# usbToTTLByPL2303_6.net
KiCad netlist of a schematic drawn in Altium Designer
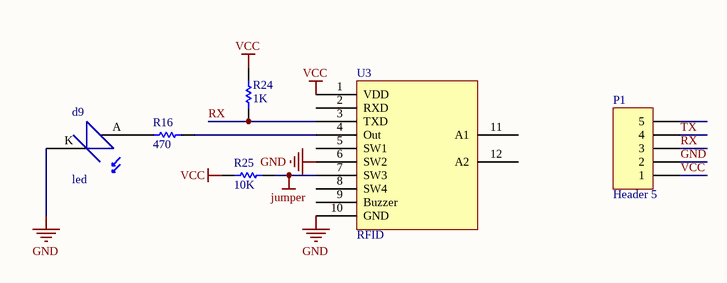
[diagram p0: usbToTTLByPL2303_6.SchDoc]

(export (version "E")
  (design (tool "Eeschema 10.0.6"))
  (components
    (comp (ref "d9") (value "led") (footprint "LED5") (libsource (lib "SchLib306") (part "led")))
    (comp (ref "P1")
      (value "Header 5")
      (footprint "HDR1X5")
      (description "Header, 5-Pin")
      (fields (field (name "PUBLISHER") "Altium Limited"))
      (libsource (lib "Miscellaneous Connectors") (part "Header 5"))
    )
    (comp (ref "R16")
      (value "470")
      (footprint "1206_smd")
      (description "Resistor")
      (fields (field (name "PUBLISHER") "Altium Limited"))
      (libsource (lib "Miscellaneous Devices") (part "Res1"))
    )
    (comp (ref "R24")
      (value "1K")
      (footprint "1206_smd")
      (description "Resistor")
      (fields (field (name "PUBLISHER") "Altium Limited"))
      (libsource (lib "Miscellaneous Devices") (part "Res1"))
    )
    (comp (ref "R25")
      (value "10K")
      (footprint "1206_smd")
      (description "Resistor")
      (fields (field (name "PUBLISHER") "Altium Limited"))
      (libsource (lib "Miscellaneous Devices") (part "Res1"))
    )
    (comp (ref "U3") (value "RFID") (footprint "rf") (libsource (lib "SchLib306") (part "RFID module")))
  )
  (nets
    (net (code "1") (name "/RX") (class "Default")
      (node (ref "P1") (pin "3") (pinfunction "3_3") (pintype "passive"))
      (node (ref "R24") (pin "1") (pinfunction "1_1") (pintype "passive"))
      (node (ref "U3") (pin "3") (pinfunction "TXD_3") (pintype "passive"))
    )
    (net (code "2") (name "/TX") (class "Default")
      (node (ref "P1") (pin "4") (pinfunction "4_4") (pintype "passive"))
    )
    (net (code "3") (name "GND") (class "Default")
      (node (ref "P1") (pin "2") (pinfunction "2_2") (pintype "passive"))
      (node (ref "U3") (pin "10") (pinfunction "GND_10") (pintype "passive"))
      (node (ref "U3") (pin "6") (pinfunction "SW2_6") (pintype "passive"))
      (node (ref "d9") (pin "K") (pintype "passive"))
    )
    (net (code "4") (name "Net-(R16-Pad1)") (class "Default")
      (node (ref "R16") (pin "1") (pinfunction "1_1") (pintype "passive"))
      (node (ref "d9") (pin "A") (pintype "passive"))
    )
    (net (code "5") (name "Net-(U3-Out)") (class "Default")
      (node (ref "R16") (pin "2") (pinfunction "2_2") (pintype "passive"))
      (node (ref "U3") (pin "4") (pinfunction "Out_4") (pintype "passive"))
    )
    (net (code "6") (name "VCC") (class "Default")
      (node (ref "P1") (pin "1") (pinfunction "1_1") (pintype "passive"))
      (node (ref "R24") (pin "2") (pinfunction "2_2") (pintype "passive"))
      (node (ref "R25") (pin "2") (pinfunction "2_2") (pintype "passive"))
      (node (ref "U3") (pin "1") (pinfunction "VDD_1") (pintype "passive"))
    )
    (net (code "7") (name "jumper") (class "Default")
      (node (ref "R25") (pin "1") (pinfunction "1_1") (pintype "passive"))
      (node (ref "U3") (pin "7") (pinfunction "SW3_7") (pintype "passive"))
    )
    (net (code "8") (name "unconnected-(P1-Pad5)") (class "Default")
      (node (ref "P1") (pin "5") (pinfunction "5_5") (pintype "passive"))
    )
    (net (code "9") (name "unconnected-(U3-A1-Pad11)") (class "Default")
      (node (ref "U3") (pin "11") (pinfunction "A1_11") (pintype "passive"))
    )
    (net (code "10") (name "unconnected-(U3-A2-Pad12)") (class "Default")
      (node (ref "U3") (pin "12") (pinfunction "A2_12") (pintype "passive"))
    )
    (net (code "11") (name "unconnected-(U3-Buzzer-Pad9)") (class "Default")
      (node (ref "U3") (pin "9") (pinfunction "Buzzer_9") (pintype "passive"))
    )
    (net (code "12") (name "unconnected-(U3-RXD-Pad2)") (class "Default")
      (node (ref "U3") (pin "2") (pinfunction "RXD_2") (pintype "passive"))
    )
    (net (code "13") (name "unconnected-(U3-SW1-Pad5)") (class "Default")
      (node (ref "U3") (pin "5") (pinfunction "SW1_5") (pintype "passive"))
    )
    (net (code "14") (name "unconnected-(U3-SW4-Pad8)") (class "Default")
      (node (ref "U3") (pin "8") (pinfunction "SW4_8") (pintype "passive"))
    )
  )
)
